# Mezzanine_SD_Card.net
KiCad netlist of a schematic drawn in EAGLE
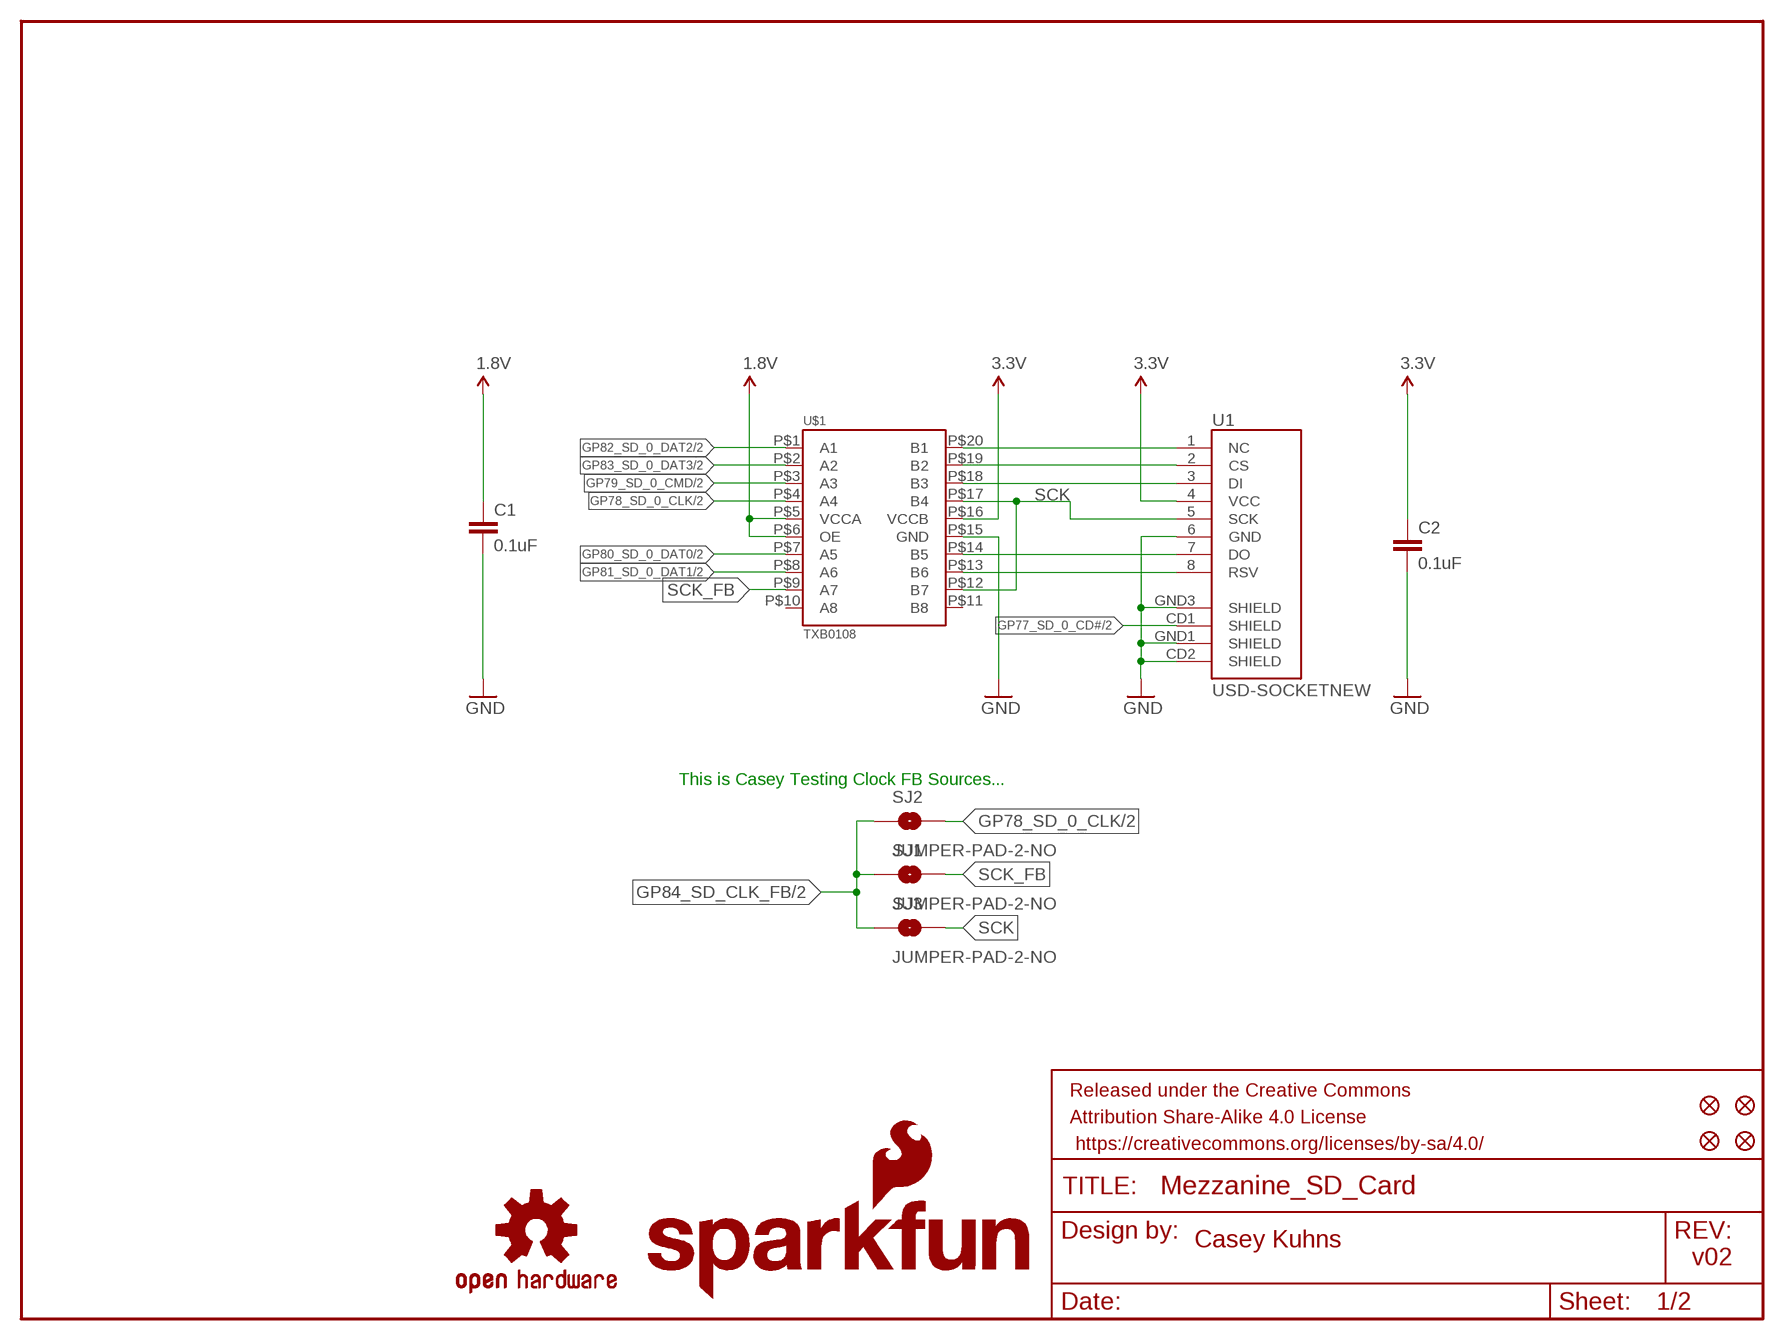
[diagram p0: schematic, sheet 1]
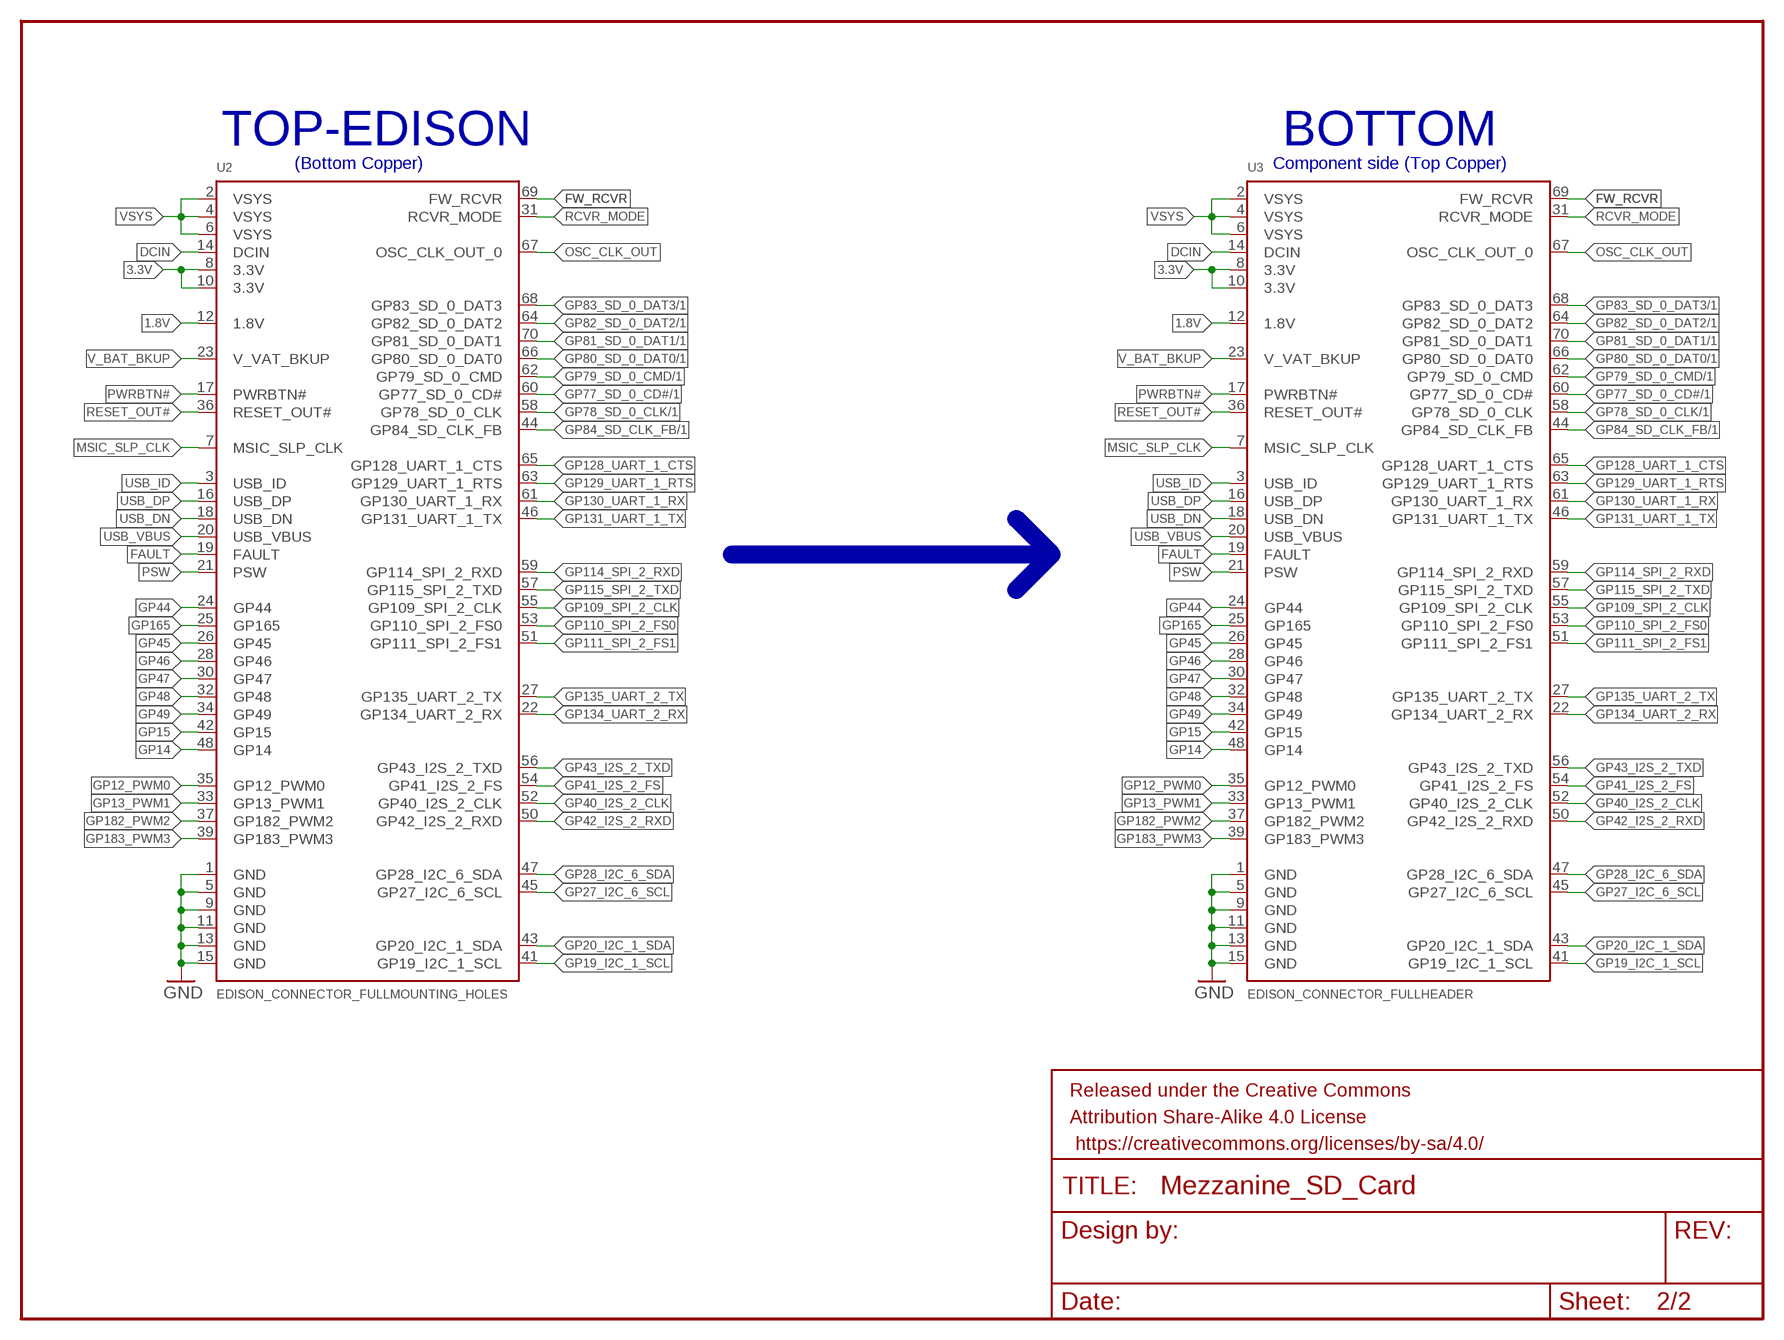
[diagram p1: schematic, sheet 2]

(export (version "E")
  (design (tool "Eeschema 10.0.6"))
  (components
    (comp (ref "C1")
      (value "0.1uF")
      (footprint "eagle-import:0603-CAP")
      (libsource (lib "eagle-import") (part "0.1UF-25V(+80/-20%)(0603)"))
    )
    (comp (ref "C2")
      (value "0.1uF")
      (footprint "eagle-import:0603-CAP")
      (libsource (lib "eagle-import") (part "0.1UF-25V(+80/-20%)(0603)"))
    )
    (comp (ref "FID1")
      (value "FIDUCIAL1X2")
      (footprint "eagle-import:FIDUCIAL-1X2")
      (libsource (lib "eagle-import") (part "FIDUCIAL1X2"))
    )
    (comp (ref "FID2")
      (value "FIDUCIAL1X2")
      (footprint "eagle-import:FIDUCIAL-1X2")
      (libsource (lib "eagle-import") (part "FIDUCIAL1X2"))
    )
    (comp (ref "FID3")
      (value "FIDUCIAL1X2")
      (footprint "eagle-import:FIDUCIAL-1X2")
      (libsource (lib "eagle-import") (part "FIDUCIAL1X2"))
    )
    (comp (ref "FID4")
      (value "FIDUCIAL1X2")
      (footprint "eagle-import:FIDUCIAL-1X2")
      (libsource (lib "eagle-import") (part "FIDUCIAL1X2"))
    )
    (comp (ref "FRAME1")
      (value "FRAME-LETTER")
      (footprint "eagle-import:CREATIVE_COMMONS")
      (libsource (lib "eagle-import") (part "FRAME-LETTER"))
    )
    (comp (ref "LOGO1")
      (value "OSHW-LOGOS")
      (footprint "eagle-import:OSHW-LOGO-S")
      (libsource (lib "eagle-import") (part "OSHW-LOGOS"))
    )
    (comp (ref "LOGO4")
      (value "SFE_LOGO_NAME_FLAME.1_INCH")
      (footprint "eagle-import:SFE_LOGO_NAME_FLAME_.1")
      (libsource (lib "eagle-import") (part "SFE_LOGO_NAME_FLAME.1_INCH"))
    )
    (comp (ref "SJ1")
      (value "JUMPER-PAD-2-NO")
      (footprint "eagle-import:PAD-JUMPER-2-NO_NO_SILK")
      (libsource (lib "eagle-import") (part "JUMPER-PAD-2-NO"))
    )
    (comp (ref "SJ2")
      (value "JUMPER-PAD-2-NO")
      (footprint "eagle-import:PAD-JUMPER-2-NO_NO_SILK")
      (libsource (lib "eagle-import") (part "JUMPER-PAD-2-NO"))
    )
    (comp (ref "SJ3")
      (value "JUMPER-PAD-2-NO")
      (footprint "eagle-import:PAD-JUMPER-2-NO_NO_SILK")
      (libsource (lib "eagle-import") (part "JUMPER-PAD-2-NO"))
    )
    (comp (ref "U$1")
      (value "TXB0108")
      (footprint "eagle-import:UFDFN-20")
      (libsource (lib "eagle-import") (part "TXB0108"))
    )
    (comp (ref "U1")
      (value "USD-SOCKETNEW")
      (footprint "eagle-import:MICRO-SD-SOCKET-PP")
      (libsource (lib "eagle-import") (part "USD-SOCKETNEW"))
    )
    (comp (ref "FRAME2")
      (value "FRAME-LETTER")
      (footprint "eagle-import:CREATIVE_COMMONS")
      (libsource (lib "eagle-import") (part "FRAME-LETTER"))
    )
    (comp (ref "U2")
      (value "EDISON_CONNECTOR_FULLMOUNTING_HOLES")
      (footprint "eagle-import:EDISON_DAUGHTER")
      (libsource (lib "eagle-import") (part "EDISON_CONNECTOR_FULLMOUNTING_HOLES"))
    )
    (comp (ref "U3")
      (value "EDISON_CONNECTOR_FULLHEADER")
      (footprint "eagle-import:DF40C-70DP-0.4(51)")
      (libsource (lib "eagle-import") (part "EDISON_CONNECTOR_FULLHEADER"))
    )
  )
  (nets
    (net (code "1") (name "1.8V") (class "Default")
      (node (ref "C1") (pin "1") (pinfunction "1_1") (pintype "passive"))
      (node (ref "U$1") (pin "P$5") (pinfunction "VCCA_P$5") (pintype "bidirectional"))
      (node (ref "U$1") (pin "P$6") (pinfunction "OE_P$6") (pintype "bidirectional"))
      (node (ref "U2") (pin "12") (pinfunction "1.8V_12") (pintype "bidirectional"))
      (node (ref "U3") (pin "12") (pinfunction "1.8V_12") (pintype "bidirectional"))
    )
    (net (code "2") (name "3.3V") (class "Default")
      (node (ref "C2") (pin "1") (pinfunction "1_1") (pintype "passive"))
      (node (ref "U$1") (pin "P$16") (pinfunction "VCCB_P$16") (pintype "bidirectional"))
      (node (ref "U1") (pin "4") (pinfunction "VCC_4") (pintype "bidirectional"))
      (node (ref "U2") (pin "10") (pinfunction "3.3V_10") (pintype "bidirectional"))
      (node (ref "U2") (pin "8") (pinfunction "3.3V_8") (pintype "bidirectional"))
      (node (ref "U3") (pin "10") (pinfunction "3.3V_10") (pintype "bidirectional"))
      (node (ref "U3") (pin "8") (pinfunction "3.3V_8") (pintype "bidirectional"))
    )
    (net (code "3") (name "DCIN") (class "Default")
      (node (ref "U2") (pin "14") (pinfunction "DCIN_14") (pintype "bidirectional"))
      (node (ref "U3") (pin "14") (pinfunction "DCIN_14") (pintype "bidirectional"))
    )
    (net (code "4") (name "FAULT") (class "Default")
      (node (ref "U2") (pin "19") (pinfunction "FAULT_19") (pintype "bidirectional"))
      (node (ref "U3") (pin "19") (pinfunction "FAULT_19") (pintype "bidirectional"))
    )
    (net (code "5") (name "FW_RCVR") (class "Default")
      (node (ref "U2") (pin "69") (pinfunction "FW_RCVR_69") (pintype "bidirectional"))
      (node (ref "U3") (pin "69") (pinfunction "FW_RCVR_69") (pintype "bidirectional"))
    )
    (net (code "6") (name "GND") (class "Default")
      (node (ref "C1") (pin "2") (pinfunction "2_2") (pintype "passive"))
      (node (ref "C2") (pin "2") (pinfunction "2_2") (pintype "passive"))
      (node (ref "U$1") (pin "P$15") (pinfunction "GND_P$15") (pintype "bidirectional"))
      (node (ref "U1") (pin "6") (pinfunction "GND_6") (pintype "bidirectional"))
      (node (ref "U1") (pin "CD2") (pinfunction "SHIELD_CD2") (pintype "bidirectional"))
      (node (ref "U1") (pin "GND1") (pinfunction "SHIELD_GND1") (pintype "bidirectional"))
      (node (ref "U1") (pin "GND3") (pinfunction "SHIELD_GND3") (pintype "bidirectional"))
      (node (ref "U2") (pin "1") (pinfunction "GND_1") (pintype "bidirectional"))
      (node (ref "U2") (pin "11") (pinfunction "GND_11") (pintype "bidirectional"))
      (node (ref "U2") (pin "13") (pinfunction "GND_13") (pintype "bidirectional"))
      (node (ref "U2") (pin "15") (pinfunction "GND_15") (pintype "bidirectional"))
      (node (ref "U2") (pin "5") (pinfunction "GND_5") (pintype "bidirectional"))
      (node (ref "U2") (pin "9") (pinfunction "GND_9") (pintype "bidirectional"))
      (node (ref "U3") (pin "1") (pinfunction "GND_1") (pintype "bidirectional"))
      (node (ref "U3") (pin "11") (pinfunction "GND_11") (pintype "bidirectional"))
      (node (ref "U3") (pin "13") (pinfunction "GND_13") (pintype "bidirectional"))
      (node (ref "U3") (pin "15") (pinfunction "GND_15") (pintype "bidirectional"))
      (node (ref "U3") (pin "5") (pinfunction "GND_5") (pintype "bidirectional"))
      (node (ref "U3") (pin "9") (pinfunction "GND_9") (pintype "bidirectional"))
    )
    (net (code "7") (name "GP12_PWM0") (class "Default")
      (node (ref "U2") (pin "35") (pinfunction "GP12_PWM0_35") (pintype "bidirectional"))
      (node (ref "U3") (pin "35") (pinfunction "GP12_PWM0_35") (pintype "bidirectional"))
    )
    (net (code "8") (name "GP13_PWM1") (class "Default")
      (node (ref "U2") (pin "33") (pinfunction "GP13_PWM1_33") (pintype "bidirectional"))
      (node (ref "U3") (pin "33") (pinfunction "GP13_PWM1_33") (pintype "bidirectional"))
    )
    (net (code "9") (name "GP14") (class "Default")
      (node (ref "U2") (pin "48") (pinfunction "GP14_48") (pintype "bidirectional"))
      (node (ref "U3") (pin "48") (pinfunction "GP14_48") (pintype "bidirectional"))
    )
    (net (code "10") (name "GP15") (class "Default")
      (node (ref "U2") (pin "42") (pinfunction "GP15_42") (pintype "bidirectional"))
      (node (ref "U3") (pin "42") (pinfunction "GP15_42") (pintype "bidirectional"))
    )
    (net (code "11") (name "GP19_I2C_1_SCL") (class "Default")
      (node (ref "U2") (pin "41") (pinfunction "GP19_I2C_1_SCL_41") (pintype "bidirectional"))
      (node (ref "U3") (pin "41") (pinfunction "GP19_I2C_1_SCL_41") (pintype "bidirectional"))
    )
    (net (code "12") (name "GP20_I2C_1_SDA") (class "Default")
      (node (ref "U2") (pin "43") (pinfunction "GP20_I2C_1_SDA_43") (pintype "bidirectional"))
      (node (ref "U3") (pin "43") (pinfunction "GP20_I2C_1_SDA_43") (pintype "bidirectional"))
    )
    (net (code "13") (name "GP27_I2C_6_SCL") (class "Default")
      (node (ref "U2") (pin "45") (pinfunction "GP27_I2C_6_SCL_45") (pintype "bidirectional"))
      (node (ref "U3") (pin "45") (pinfunction "GP27_I2C_6_SCL_45") (pintype "bidirectional"))
    )
    (net (code "14") (name "GP28_I2C_6_SDA") (class "Default")
      (node (ref "U2") (pin "47") (pinfunction "GP28_I2C_6_SDA_47") (pintype "bidirectional"))
      (node (ref "U3") (pin "47") (pinfunction "GP28_I2C_6_SDA_47") (pintype "bidirectional"))
    )
    (net (code "15") (name "GP40_I2S_2_CLK") (class "Default")
      (node (ref "U2") (pin "52") (pinfunction "GP40_I2S_2_CLK_52") (pintype "bidirectional"))
      (node (ref "U3") (pin "52") (pinfunction "GP40_I2S_2_CLK_52") (pintype "bidirectional"))
    )
    (net (code "16") (name "GP41_I2S_2_FS") (class "Default")
      (node (ref "U2") (pin "54") (pinfunction "GP41_I2S_2_FS_54") (pintype "bidirectional"))
      (node (ref "U3") (pin "54") (pinfunction "GP41_I2S_2_FS_54") (pintype "bidirectional"))
    )
    (net (code "17") (name "GP42_I2S_2_RXD") (class "Default")
      (node (ref "U2") (pin "50") (pinfunction "GP42_I2S_2_RXD_50") (pintype "bidirectional"))
      (node (ref "U3") (pin "50") (pinfunction "GP42_I2S_2_RXD_50") (pintype "bidirectional"))
    )
    (net (code "18") (name "GP43_I2S_2_TXD") (class "Default")
      (node (ref "U2") (pin "56") (pinfunction "GP43_I2S_2_TXD_56") (pintype "bidirectional"))
      (node (ref "U3") (pin "56") (pinfunction "GP43_I2S_2_TXD_56") (pintype "bidirectional"))
    )
    (net (code "19") (name "GP44") (class "Default")
      (node (ref "U2") (pin "24") (pinfunction "GP44_24") (pintype "bidirectional"))
      (node (ref "U3") (pin "24") (pinfunction "GP44_24") (pintype "bidirectional"))
    )
    (net (code "20") (name "GP45") (class "Default")
      (node (ref "U2") (pin "26") (pinfunction "GP45_26") (pintype "bidirectional"))
      (node (ref "U3") (pin "26") (pinfunction "GP45_26") (pintype "bidirectional"))
    )
    (net (code "21") (name "GP46") (class "Default")
      (node (ref "U2") (pin "28") (pinfunction "GP46_28") (pintype "bidirectional"))
      (node (ref "U3") (pin "28") (pinfunction "GP46_28") (pintype "bidirectional"))
    )
    (net (code "22") (name "GP47") (class "Default")
      (node (ref "U2") (pin "30") (pinfunction "GP47_30") (pintype "bidirectional"))
      (node (ref "U3") (pin "30") (pinfunction "GP47_30") (pintype "bidirectional"))
    )
    (net (code "23") (name "GP48") (class "Default")
      (node (ref "U2") (pin "32") (pinfunction "GP48_32") (pintype "bidirectional"))
      (node (ref "U3") (pin "32") (pinfunction "GP48_32") (pintype "bidirectional"))
    )
    (net (code "24") (name "GP49") (class "Default")
      (node (ref "U2") (pin "34") (pinfunction "GP49_34") (pintype "bidirectional"))
      (node (ref "U3") (pin "34") (pinfunction "GP49_34") (pintype "bidirectional"))
    )
    (net (code "25") (name "GP77_SD_0_CD#") (class "Default")
      (node (ref "U1") (pin "CD1") (pinfunction "SHIELD_CD1") (pintype "bidirectional"))
      (node (ref "U2") (pin "60") (pinfunction "GP77_SD_0_CD#_60") (pintype "bidirectional"))
      (node (ref "U3") (pin "60") (pinfunction "GP77_SD_0_CD#_60") (pintype "bidirectional"))
    )
    (net (code "26") (name "GP78_SD_0_CLK") (class "Default")
      (node (ref "SJ2") (pin "2") (pinfunction "2_2") (pintype "passive"))
      (node (ref "U$1") (pin "P$4") (pinfunction "A4_P$4") (pintype "bidirectional"))
      (node (ref "U2") (pin "58") (pinfunction "GP78_SD_0_CLK_58") (pintype "bidirectional"))
      (node (ref "U3") (pin "58") (pinfunction "GP78_SD_0_CLK_58") (pintype "bidirectional"))
    )
    (net (code "27") (name "GP79_SD_0_CMD") (class "Default")
      (node (ref "U$1") (pin "P$3") (pinfunction "A3_P$3") (pintype "bidirectional"))
      (node (ref "U2") (pin "62") (pinfunction "GP79_SD_0_CMD_62") (pintype "bidirectional"))
      (node (ref "U3") (pin "62") (pinfunction "GP79_SD_0_CMD_62") (pintype "bidirectional"))
    )
    (net (code "28") (name "GP80_SD_0_DAT0") (class "Default")
      (node (ref "U$1") (pin "P$7") (pinfunction "A5_P$7") (pintype "bidirectional"))
      (node (ref "U2") (pin "66") (pinfunction "GP80_SD_0_DAT0_66") (pintype "bidirectional"))
      (node (ref "U3") (pin "66") (pinfunction "GP80_SD_0_DAT0_66") (pintype "bidirectional"))
    )
    (net (code "29") (name "GP81_SD_0_DAT1") (class "Default")
      (node (ref "U$1") (pin "P$8") (pinfunction "A6_P$8") (pintype "bidirectional"))
      (node (ref "U2") (pin "70") (pinfunction "GP81_SD_0_DAT1_70") (pintype "bidirectional"))
      (node (ref "U3") (pin "70") (pinfunction "GP81_SD_0_DAT1_70") (pintype "bidirectional"))
    )
    (net (code "30") (name "GP82_SD_0_DAT2") (class "Default")
      (node (ref "U$1") (pin "P$1") (pinfunction "A1_P$1") (pintype "bidirectional"))
      (node (ref "U2") (pin "64") (pinfunction "GP82_SD_0_DAT2_64") (pintype "bidirectional"))
      (node (ref "U3") (pin "64") (pinfunction "GP82_SD_0_DAT2_64") (pintype "bidirectional"))
    )
    (net (code "31") (name "GP83_SD_0_DAT3") (class "Default")
      (node (ref "U$1") (pin "P$2") (pinfunction "A2_P$2") (pintype "bidirectional"))
      (node (ref "U2") (pin "68") (pinfunction "GP83_SD_0_DAT3_68") (pintype "bidirectional"))
      (node (ref "U3") (pin "68") (pinfunction "GP83_SD_0_DAT3_68") (pintype "bidirectional"))
    )
    (net (code "32") (name "GP84_SD_CLK_FB") (class "Default")
      (node (ref "SJ1") (pin "1") (pinfunction "1_1") (pintype "passive"))
      (node (ref "SJ2") (pin "1") (pinfunction "1_1") (pintype "passive"))
      (node (ref "SJ3") (pin "1") (pinfunction "1_1") (pintype "passive"))
      (node (ref "U2") (pin "44") (pinfunction "GP84_SD_CLK_FB_44") (pintype "bidirectional"))
      (node (ref "U3") (pin "44") (pinfunction "GP84_SD_CLK_FB_44") (pintype "bidirectional"))
    )
    (net (code "33") (name "GP109_SPI_2_CLK") (class "Default")
      (node (ref "U2") (pin "55") (pinfunction "GP109_SPI_2_CLK_55") (pintype "bidirectional"))
      (node (ref "U3") (pin "55") (pinfunction "GP109_SPI_2_CLK_55") (pintype "bidirectional"))
    )
    (net (code "34") (name "GP110_SPI_2_FS0") (class "Default")
      (node (ref "U2") (pin "53") (pinfunction "GP110_SPI_2_FS0_53") (pintype "bidirectional"))
      (node (ref "U3") (pin "53") (pinfunction "GP110_SPI_2_FS0_53") (pintype "bidirectional"))
    )
    (net (code "35") (name "GP111_SPI_2_FS1") (class "Default")
      (node (ref "U2") (pin "51") (pinfunction "GP111_SPI_2_FS1_51") (pintype "bidirectional"))
      (node (ref "U3") (pin "51") (pinfunction "GP111_SPI_2_FS1_51") (pintype "bidirectional"))
    )
    (net (code "36") (name "GP114_SPI_2_RXD") (class "Default")
      (node (ref "U2") (pin "59") (pinfunction "GP114_SPI_2_RXD_59") (pintype "bidirectional"))
      (node (ref "U3") (pin "59") (pinfunction "GP114_SPI_2_RXD_59") (pintype "bidirectional"))
    )
    (net (code "37") (name "GP115_SPI_2_TXD") (class "Default")
      (node (ref "U2") (pin "57") (pinfunction "GP115_SPI_2_TXD_57") (pintype "bidirectional"))
      (node (ref "U3") (pin "57") (pinfunction "GP115_SPI_2_TXD_57") (pintype "bidirectional"))
    )
    (net (code "38") (name "GP128_UART_1_CTS") (class "Default")
      (node (ref "U2") (pin "65") (pinfunction "GP128_UART_1_CTS_65") (pintype "bidirectional"))
      (node (ref "U3") (pin "65") (pinfunction "GP128_UART_1_CTS_65") (pintype "bidirectional"))
    )
    (net (code "39") (name "GP129_UART_1_RTS") (class "Default")
      (node (ref "U2") (pin "63") (pinfunction "GP129_UART_1_RTS_63") (pintype "bidirectional"))
      (node (ref "U3") (pin "63") (pinfunction "GP129_UART_1_RTS_63") (pintype "bidirectional"))
    )
    (net (code "40") (name "GP130_UART_1_RX") (class "Default")
      (node (ref "U2") (pin "61") (pinfunction "GP130_UART_1_RX_61") (pintype "bidirectional"))
      (node (ref "U3") (pin "61") (pinfunction "GP130_UART_1_RX_61") (pintype "bidirectional"))
    )
    (net (code "41") (name "GP131_UART_1_TX") (class "Default")
      (node (ref "U2") (pin "46") (pinfunction "GP131_UART_1_TX_46") (pintype "bidirectional"))
      (node (ref "U3") (pin "46") (pinfunction "GP131_UART_1_TX_46") (pintype "bidirectional"))
    )
    (net (code "42") (name "GP134_UART_2_RX") (class "Default")
      (node (ref "U2") (pin "22") (pinfunction "GP134_UART_2_RX_22") (pintype "bidirectional"))
      (node (ref "U3") (pin "22") (pinfunction "GP134_UART_2_RX_22") (pintype "bidirectional"))
    )
    (net (code "43") (name "GP135_UART_2_TX") (class "Default")
      (node (ref "U2") (pin "27") (pinfunction "GP135_UART_2_TX_27") (pintype "bidirectional"))
      (node (ref "U3") (pin "27") (pinfunction "GP135_UART_2_TX_27") (pintype "bidirectional"))
    )
    (net (code "44") (name "GP165") (class "Default")
      (node (ref "U2") (pin "25") (pinfunction "GP165_25") (pintype "bidirectional"))
      (node (ref "U3") (pin "25") (pinfunction "GP165_25") (pintype "bidirectional"))
    )
    (net (code "45") (name "GP182_PWM2") (class "Default")
      (node (ref "U2") (pin "37") (pinfunction "GP182_PWM2_37") (pintype "bidirectional"))
      (node (ref "U3") (pin "37") (pinfunction "GP182_PWM2_37") (pintype "bidirectional"))
    )
    (net (code "46") (name "GP183_PWM3") (class "Default")
      (node (ref "U2") (pin "39") (pinfunction "GP183_PWM3_39") (pintype "bidirectional"))
      (node (ref "U3") (pin "39") (pinfunction "GP183_PWM3_39") (pintype "bidirectional"))
    )
    (net (code "47") (name "MSIC_SLP_CLK") (class "Default")
      (node (ref "U2") (pin "7") (pinfunction "MSIC_SLP_CLK_7") (pintype "bidirectional"))
      (node (ref "U3") (pin "7") (pinfunction "MSIC_SLP_CLK_7") (pintype "bidirectional"))
    )
    (net (code "48") (name "Net-(U$1-B1)") (class "Default")
      (node (ref "U$1") (pin "P$20") (pinfunction "B1_P$20") (pintype "bidirectional"))
      (node (ref "U1") (pin "1") (pinfunction "NC_1") (pintype "bidirectional"))
    )
    (net (code "49") (name "Net-(U$1-B2)") (class "Default")
      (node (ref "U$1") (pin "P$19") (pinfunction "B2_P$19") (pintype "bidirectional"))
      (node (ref "U1") (pin "2") (pinfunction "CS_2") (pintype "bidirectional"))
    )
    (net (code "50") (name "Net-(U$1-B3)") (class "Default")
      (node (ref "U$1") (pin "P$18") (pinfunction "B3_P$18") (pintype "bidirectional"))
      (node (ref "U1") (pin "3") (pinfunction "DI_3") (pintype "bidirectional"))
    )
    (net (code "51") (name "Net-(U$1-B5)") (class "Default")
      (node (ref "U$1") (pin "P$14") (pinfunction "B5_P$14") (pintype "bidirectional"))
      (node (ref "U1") (pin "7") (pinfunction "DO_7") (pintype "bidirectional"))
    )
    (net (code "52") (name "Net-(U$1-B6)") (class "Default")
      (node (ref "U$1") (pin "P$13") (pinfunction "B6_P$13") (pintype "bidirectional"))
      (node (ref "U1") (pin "8") (pinfunction "RSV_8") (pintype "bidirectional"))
    )
    (net (code "53") (name "OSC_CLK_OUT") (class "Default")
      (node (ref "U2") (pin "67") (pinfunction "OSC_CLK_OUT_0_67") (pintype "bidirectional"))
      (node (ref "U3") (pin "67") (pinfunction "OSC_CLK_OUT_0_67") (pintype "bidirectional"))
    )
    (net (code "54") (name "PSW") (class "Default")
      (node (ref "U2") (pin "21") (pinfunction "PSW_21") (pintype "bidirectional"))
      (node (ref "U3") (pin "21") (pinfunction "PSW_21") (pintype "bidirectional"))
    )
    (net (code "55") (name "PWRBTN#") (class "Default")
      (node (ref "U2") (pin "17") (pinfunction "PWRBTN#_17") (pintype "bidirectional"))
      (node (ref "U3") (pin "17") (pinfunction "PWRBTN#_17") (pintype "bidirectional"))
    )
    (net (code "56") (name "RCVR_MODE") (class "Default")
      (node (ref "U2") (pin "31") (pinfunction "RCVR_MODE_31") (pintype "bidirectional"))
      (node (ref "U3") (pin "31") (pinfunction "RCVR_MODE_31") (pintype "bidirectional"))
    )
    (net (code "57") (name "RESET_OUT#") (class "Default")
      (node (ref "U2") (pin "36") (pinfunction "RESET_OUT#_36") (pintype "bidirectional"))
      (node (ref "U3") (pin "36") (pinfunction "RESET_OUT#_36") (pintype "bidirectional"))
    )
    (net (code "58") (name "SCK") (class "Default")
      (node (ref "SJ3") (pin "2") (pinfunction "2_2") (pintype "passive"))
      (node (ref "U$1") (pin "P$12") (pinfunction "B7_P$12") (pintype "bidirectional"))
      (node (ref "U$1") (pin "P$17") (pinfunction "B4_P$17") (pintype "bidirectional"))
      (node (ref "U1") (pin "5") (pinfunction "SCK_5") (pintype "bidirectional"))
    )
    (net (code "59") (name "SCK_FB") (class "Default")
      (node (ref "SJ1") (pin "2") (pinfunction "2_2") (pintype "passive"))
      (node (ref "U$1") (pin "P$9") (pinfunction "A7_P$9") (pintype "bidirectional"))
    )
    (net (code "60") (name "USB_DN") (class "Default")
      (node (ref "U2") (pin "18") (pinfunction "USB_DN_18") (pintype "bidirectional"))
      (node (ref "U3") (pin "18") (pinfunction "USB_DN_18") (pintype "bidirectional"))
    )
    (net (code "61") (name "USB_DP") (class "Default")
      (node (ref "U2") (pin "16") (pinfunction "USB_DP_16") (pintype "bidirectional"))
      (node (ref "U3") (pin "16") (pinfunction "USB_DP_16") (pintype "bidirectional"))
    )
    (net (code "62") (name "USB_ID") (class "Default")
      (node (ref "U2") (pin "3") (pinfunction "USB_ID_3") (pintype "bidirectional"))
      (node (ref "U3") (pin "3") (pinfunction "USB_ID_3") (pintype "bidirectional"))
    )
    (net (code "63") (name "USB_VBUS") (class "Default")
      (node (ref "U2") (pin "20") (pinfunction "USB_VBUS_20") (pintype "bidirectional"))
      (node (ref "U3") (pin "20") (pinfunction "USB_VBUS_20") (pintype "bidirectional"))
    )
    (net (code "64") (name "VSYS") (class "Default")
      (node (ref "U2") (pin "2") (pinfunction "VSYS_2") (pintype "bidirectional"))
      (node (ref "U2") (pin "4") (pinfunction "VSYS_4") (pintype "bidirectional"))
      (node (ref "U2") (pin "6") (pinfunction "VSYS_6") (pintype "bidirectional"))
      (node (ref "U3") (pin "2") (pinfunction "VSYS_2") (pintype "bidirectional"))
      (node (ref "U3") (pin "4") (pinfunction "VSYS_4") (pintype "bidirectional"))
      (node (ref "U3") (pin "6") (pinfunction "VSYS_6") (pintype "bidirectional"))
    )
    (net (code "65") (name "V_BAT_BKUP") (class "Default")
      (node (ref "U2") (pin "23") (pinfunction "V_VAT_BKUP_23") (pintype "bidirectional"))
      (node (ref "U3") (pin "23") (pinfunction "V_VAT_BKUP_23") (pintype "bidirectional"))
    )
    (net (code "66") (name "unconnected-(U$1-A8-PadP$10)") (class "Default")
      (node (ref "U$1") (pin "P$10") (pinfunction "A8_P$10") (pintype "bidirectional"))
    )
    (net (code "67") (name "unconnected-(U$1-B8-PadP$11)") (class "Default")
      (node (ref "U$1") (pin "P$11") (pinfunction "B8_P$11") (pintype "bidirectional"))
    )
  )
)
